# PocketChipBrd.net
KiCad netlist of a schematic drawn in EAGLE
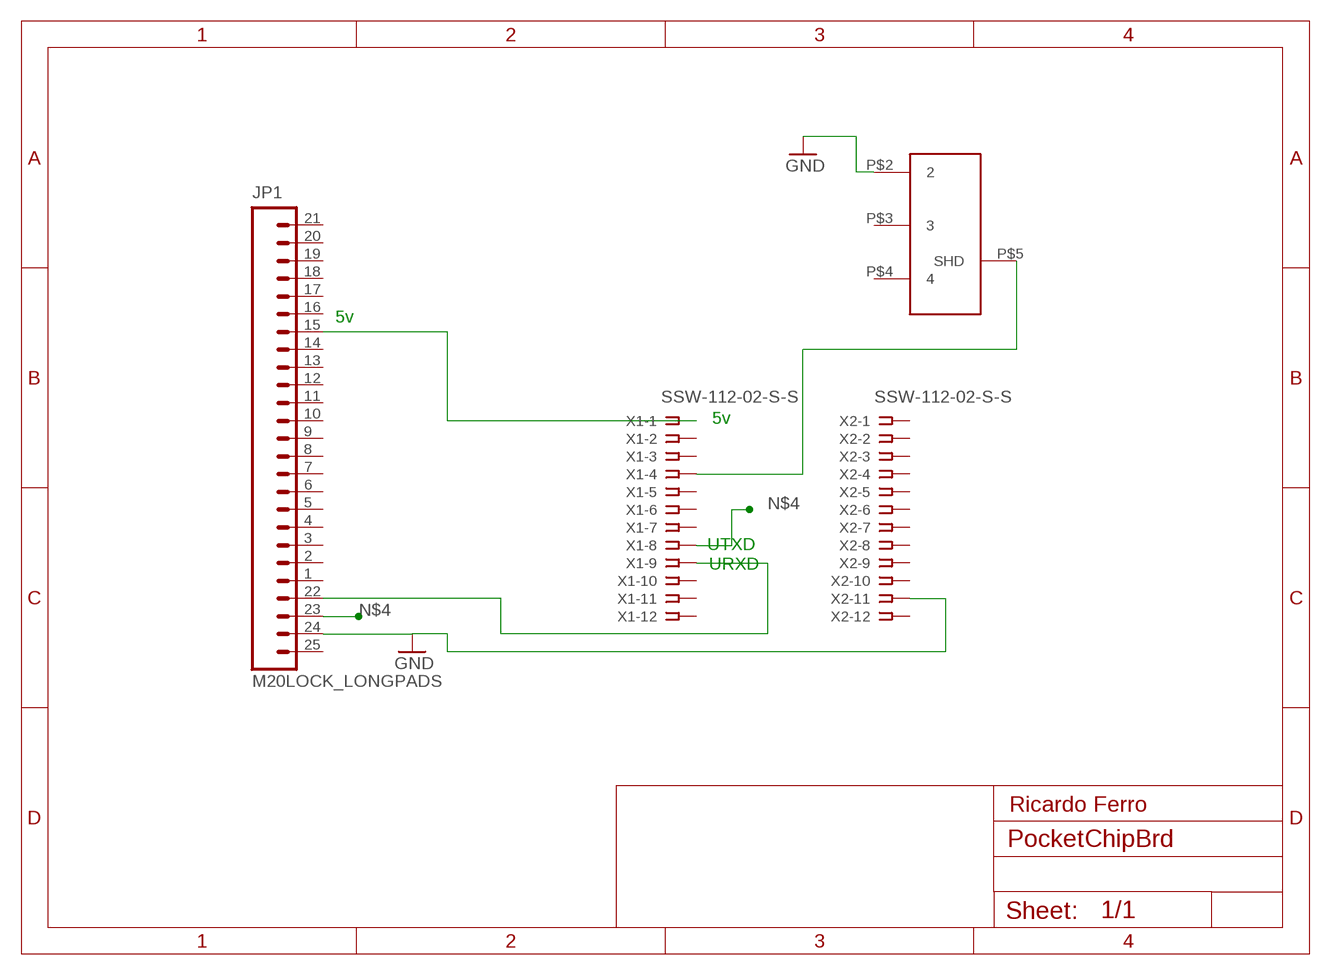
[diagram p0: schematic, sheet 1]

(export (version "E")
  (design (tool "Eeschema 10.0.6"))
  (components
    (comp (ref "JP1")
      (value "M20LOCK_LONGPADS")
      (footprint "eagle-import:1X20_LOCK_LONGPADS")
      (libsource (lib "eagle-import") (part "M20LOCK_LONGPADS"))
    )
    (comp (ref "U$1")
      (value "PJ-320D")
      (footprint "eagle-import:PJ-320D")
      (libsource (lib "eagle-import") (part "PJ-320D"))
    )
    (comp (ref "X1")
      (value "SSW-112-02-S-S")
      (footprint "eagle-import:SSW-112-02-S-S")
      (libsource (lib "eagle-import") (part "SSW-112-02-S-S"))
    )
    (comp (ref "X2")
      (value "SSW-112-02-S-S")
      (footprint "eagle-import:SSW-112-02-S-S")
      (libsource (lib "eagle-import") (part "SSW-112-02-S-S"))
    )
  )
  (nets
    (net (code "1") (name "/N$4") (class "Default")
      (node (ref "JP1") (pin "23") (pinfunction "23_23") (pintype "passive"))
      (node (ref "X1") (pin "8") (pinfunction "1_8") (pintype "passive"))
    )
    (net (code "2") (name "GND") (class "Default")
      (node (ref "JP1") (pin "24") (pinfunction "24_24") (pintype "passive"))
      (node (ref "U$1") (pin "P$2") (pinfunction "2_P$2") (pintype "bidirectional"))
      (node (ref "X2") (pin "11") (pinfunction "1_11") (pintype "passive"))
    )
    (net (code "3") (name "Net-(JP1-Pad15)") (class "Default")
      (node (ref "JP1") (pin "15") (pinfunction "15_15") (pintype "passive"))
      (node (ref "X1") (pin "1") (pinfunction "1_1") (pintype "passive"))
    )
    (net (code "4") (name "Net-(U$1-SHD)") (class "Default")
      (node (ref "U$1") (pin "P$5") (pinfunction "SHD_P$5") (pintype "bidirectional"))
      (node (ref "X1") (pin "4") (pinfunction "1_4") (pintype "passive"))
    )
    (net (code "5") (name "Net-(X1L-1)") (class "Default")
      (node (ref "JP1") (pin "22") (pinfunction "22_22") (pintype "passive"))
      (node (ref "X1") (pin "9") (pinfunction "1_9") (pintype "passive"))
    )
    (net (code "6") (name "unconnected-(JP1-Pad1)") (class "Default")
      (node (ref "JP1") (pin "1") (pinfunction "1_1") (pintype "passive"))
    )
    (net (code "7") (name "unconnected-(JP1-Pad2)") (class "Default")
      (node (ref "JP1") (pin "2") (pinfunction "2_2") (pintype "passive"))
    )
    (net (code "8") (name "unconnected-(JP1-Pad3)") (class "Default")
      (node (ref "JP1") (pin "3") (pinfunction "3_3") (pintype "passive"))
    )
    (net (code "9") (name "unconnected-(JP1-Pad4)") (class "Default")
      (node (ref "JP1") (pin "4") (pinfunction "4_4") (pintype "passive"))
    )
    (net (code "10") (name "unconnected-(JP1-Pad5)") (class "Default")
      (node (ref "JP1") (pin "5") (pinfunction "5_5") (pintype "passive"))
    )
    (net (code "11") (name "unconnected-(JP1-Pad6)") (class "Default")
      (node (ref "JP1") (pin "6") (pinfunction "6_6") (pintype "passive"))
    )
    (net (code "12") (name "unconnected-(JP1-Pad7)") (class "Default")
      (node (ref "JP1") (pin "7") (pinfunction "7_7") (pintype "passive"))
    )
    (net (code "13") (name "unconnected-(JP1-Pad8)") (class "Default")
      (node (ref "JP1") (pin "8") (pinfunction "8_8") (pintype "passive"))
    )
    (net (code "14") (name "unconnected-(JP1-Pad9)") (class "Default")
      (node (ref "JP1") (pin "9") (pinfunction "9_9") (pintype "passive"))
    )
    (net (code "15") (name "unconnected-(JP1-Pad10)") (class "Default")
      (node (ref "JP1") (pin "10") (pinfunction "10_10") (pintype "passive"))
    )
    (net (code "16") (name "unconnected-(JP1-Pad11)") (class "Default")
      (node (ref "JP1") (pin "11") (pinfunction "11_11") (pintype "passive"))
    )
    (net (code "17") (name "unconnected-(JP1-Pad12)") (class "Default")
      (node (ref "JP1") (pin "12") (pinfunction "12_12") (pintype "passive"))
    )
    (net (code "18") (name "unconnected-(JP1-Pad13)") (class "Default")
      (node (ref "JP1") (pin "13") (pinfunction "13_13") (pintype "passive"))
    )
    (net (code "19") (name "unconnected-(JP1-Pad14)") (class "Default")
      (node (ref "JP1") (pin "14") (pinfunction "14_14") (pintype "passive"))
    )
    (net (code "20") (name "unconnected-(JP1-Pad16)") (class "Default")
      (node (ref "JP1") (pin "16") (pinfunction "16_16") (pintype "passive"))
    )
    (net (code "21") (name "unconnected-(JP1-Pad17)") (class "Default")
      (node (ref "JP1") (pin "17") (pinfunction "17_17") (pintype "passive"))
    )
    (net (code "22") (name "unconnected-(JP1-Pad18)") (class "Default")
      (node (ref "JP1") (pin "18") (pinfunction "18_18") (pintype "passive"))
    )
    (net (code "23") (name "unconnected-(JP1-Pad19)") (class "Default")
      (node (ref "JP1") (pin "19") (pinfunction "19_19") (pintype "passive"))
    )
    (net (code "24") (name "unconnected-(JP1-Pad20)") (class "Default")
      (node (ref "JP1") (pin "20") (pinfunction "20_20") (pintype "passive"))
    )
    (net (code "25") (name "unconnected-(JP1-Pad21)") (class "Default")
      (node (ref "JP1") (pin "21") (pinfunction "21_21") (pintype "passive"))
    )
    (net (code "26") (name "unconnected-(JP1-Pad25)") (class "Default")
      (node (ref "JP1") (pin "25") (pinfunction "25_25") (pintype "passive"))
    )
    (net (code "27") (name "unconnected-(U$1-3-PadP$3)") (class "Default")
      (node (ref "U$1") (pin "P$3") (pinfunction "3_P$3") (pintype "bidirectional"))
    )
    (net (code "28") (name "unconnected-(U$1-4-PadP$4)") (class "Default")
      (node (ref "U$1") (pin "P$4") (pinfunction "4_P$4") (pintype "bidirectional"))
    )
    (net (code "29") (name "unconnected-(X1B-1-Pad10)") (class "Default")
      (node (ref "X1") (pin "10") (pinfunction "1_10") (pintype "passive"))
    )
    (net (code "30") (name "unconnected-(X1C-1-Pad11)") (class "Default")
      (node (ref "X1") (pin "11") (pinfunction "1_11") (pintype "passive"))
    )
    (net (code "31") (name "unconnected-(X1D-1-Pad12)") (class "Default")
      (node (ref "X1") (pin "12") (pinfunction "1_12") (pintype "passive"))
    )
    (net (code "32") (name "unconnected-(X1E-1-Pad2)") (class "Default")
      (node (ref "X1") (pin "2") (pinfunction "1_2") (pintype "passive"))
    )
    (net (code "33") (name "unconnected-(X1F-1-Pad3)") (class "Default")
      (node (ref "X1") (pin "3") (pinfunction "1_3") (pintype "passive"))
    )
    (net (code "34") (name "unconnected-(X1H-1-Pad5)") (class "Default")
      (node (ref "X1") (pin "5") (pinfunction "1_5") (pintype "passive"))
    )
    (net (code "35") (name "unconnected-(X1I-1-Pad6)") (class "Default")
      (node (ref "X1") (pin "6") (pinfunction "1_6") (pintype "passive"))
    )
    (net (code "36") (name "unconnected-(X1J-1-Pad7)") (class "Default")
      (node (ref "X1") (pin "7") (pinfunction "1_7") (pintype "passive"))
    )
    (net (code "37") (name "unconnected-(X2-Pad1)") (class "Default")
      (node (ref "X2") (pin "1") (pinfunction "1_1") (pintype "passive"))
    )
    (net (code "38") (name "unconnected-(X2B-1-Pad10)") (class "Default")
      (node (ref "X2") (pin "10") (pinfunction "1_10") (pintype "passive"))
    )
    (net (code "39") (name "unconnected-(X2D-1-Pad12)") (class "Default")
      (node (ref "X2") (pin "12") (pinfunction "1_12") (pintype "passive"))
    )
    (net (code "40") (name "unconnected-(X2E-1-Pad2)") (class "Default")
      (node (ref "X2") (pin "2") (pinfunction "1_2") (pintype "passive"))
    )
    (net (code "41") (name "unconnected-(X2F-1-Pad3)") (class "Default")
      (node (ref "X2") (pin "3") (pinfunction "1_3") (pintype "passive"))
    )
    (net (code "42") (name "unconnected-(X2G-1-Pad4)") (class "Default")
      (node (ref "X2") (pin "4") (pinfunction "1_4") (pintype "passive"))
    )
    (net (code "43") (name "unconnected-(X2H-1-Pad5)") (class "Default")
      (node (ref "X2") (pin "5") (pinfunction "1_5") (pintype "passive"))
    )
    (net (code "44") (name "unconnected-(X2I-1-Pad6)") (class "Default")
      (node (ref "X2") (pin "6") (pinfunction "1_6") (pintype "passive"))
    )
    (net (code "45") (name "unconnected-(X2J-1-Pad7)") (class "Default")
      (node (ref "X2") (pin "7") (pinfunction "1_7") (pintype "passive"))
    )
    (net (code "46") (name "unconnected-(X2K-1-Pad8)") (class "Default")
      (node (ref "X2") (pin "8") (pinfunction "1_8") (pintype "passive"))
    )
    (net (code "47") (name "unconnected-(X2L-1-Pad9)") (class "Default")
      (node (ref "X2") (pin "9") (pinfunction "1_9") (pintype "passive"))
    )
  )
)
